# Mouse_STM32F401.net
KiCad netlist of a schematic drawn in EAGLE
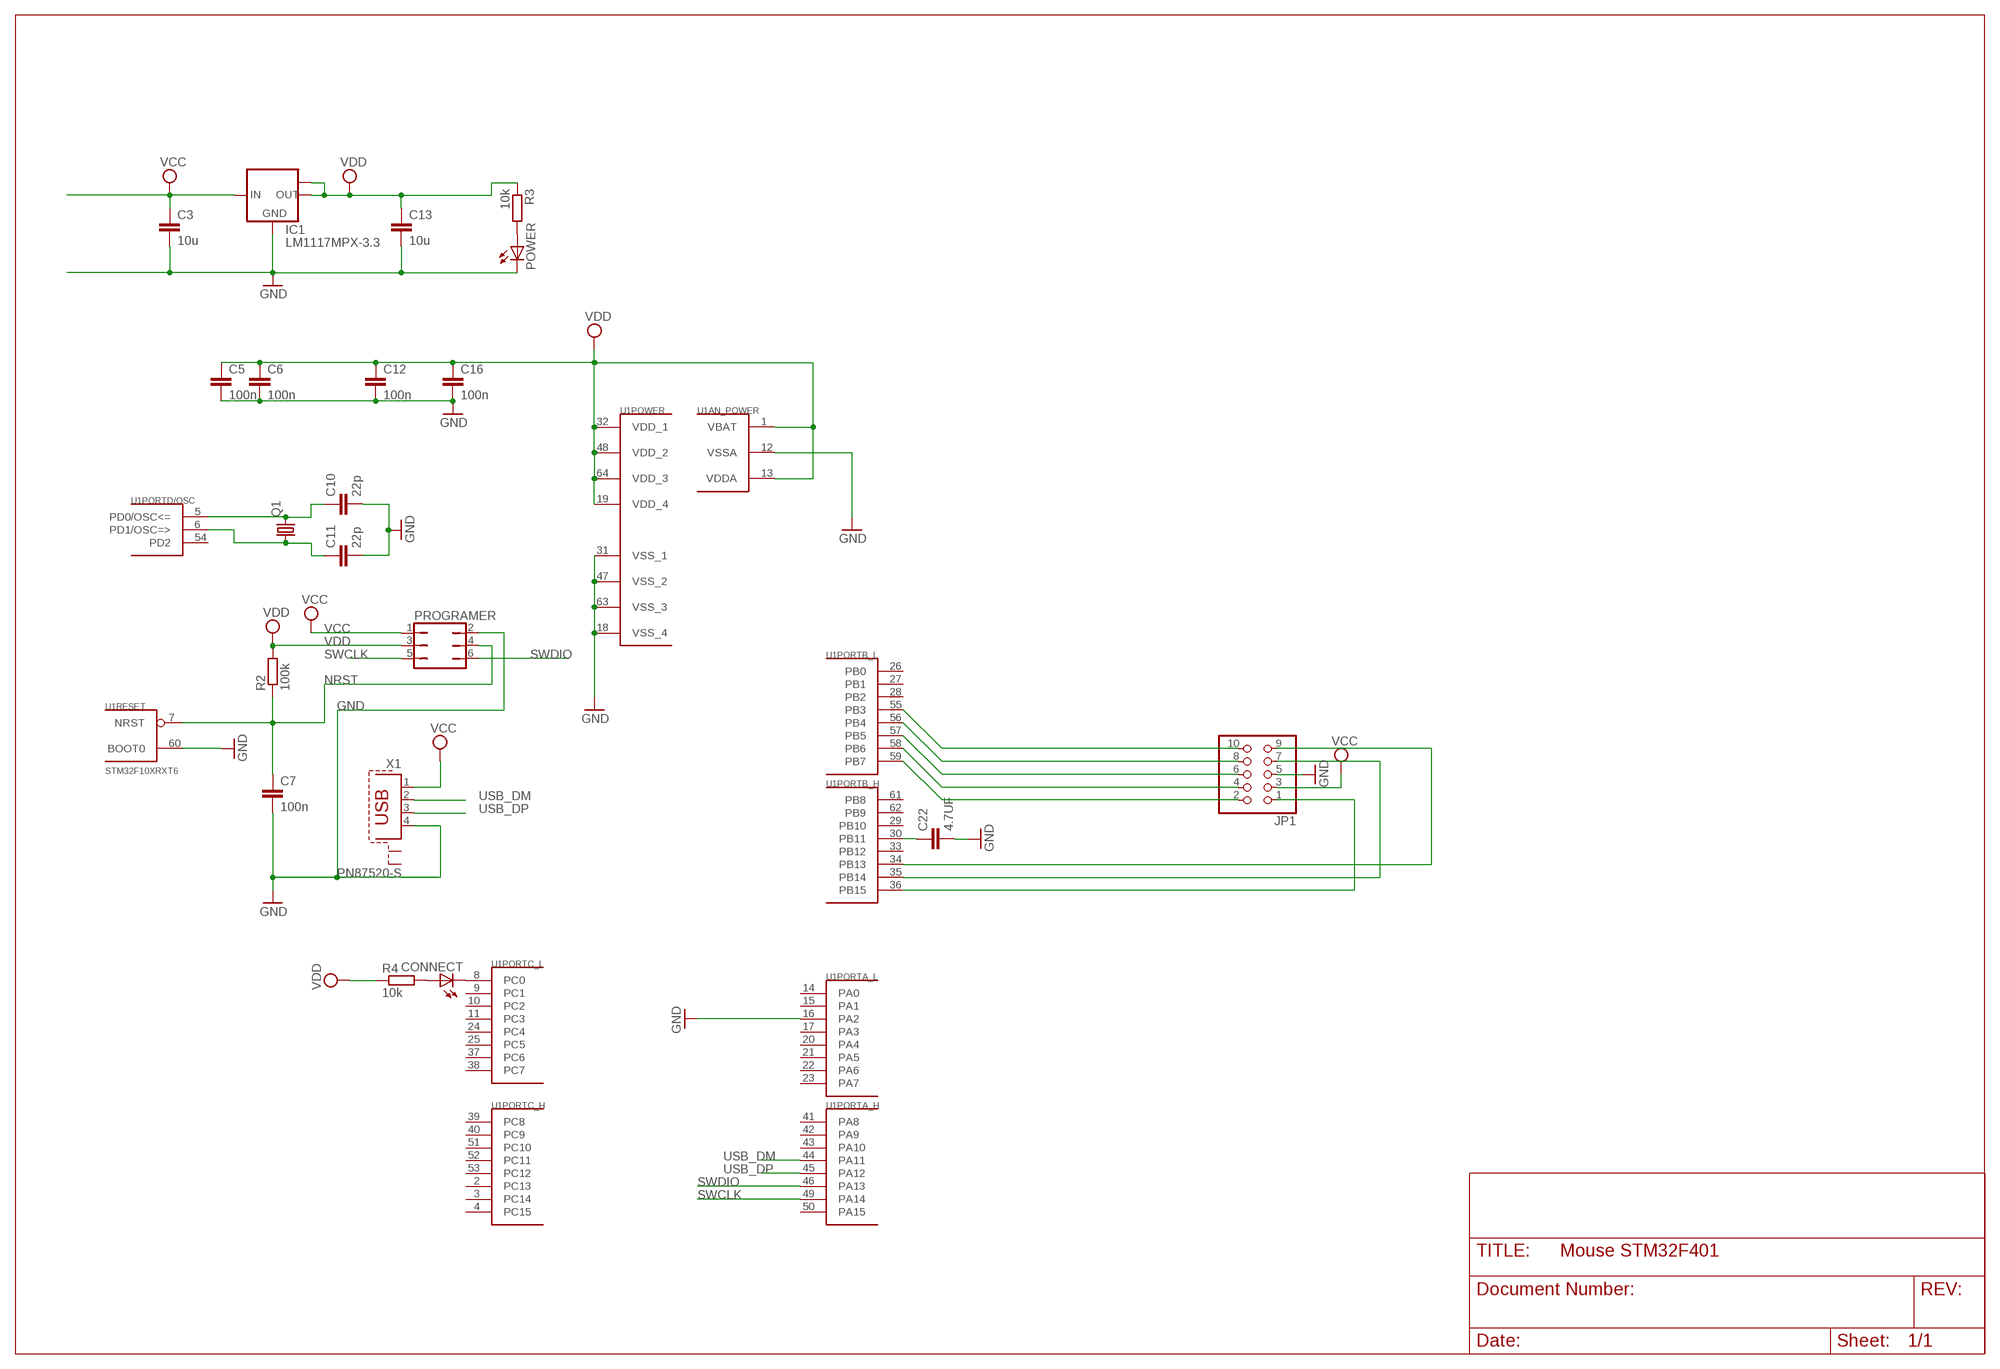
[diagram p0: schematic, sheet 1]

(export (version "E")
  (design (tool "Eeschema 10.0.6"))
  (components
    (comp (ref "C3")
      (value "10u")
      (footprint "eagle-import:C1206")
      (libsource (lib "eagle-import") (part "C-EUC1206"))
    )
    (comp (ref "C5")
      (value "100n")
      (footprint "eagle-import:C0603")
      (libsource (lib "eagle-import") (part "C-EUC0603"))
    )
    (comp (ref "C6")
      (value "100n")
      (footprint "eagle-import:C0603")
      (libsource (lib "eagle-import") (part "C-EUC0603"))
    )
    (comp (ref "C7")
      (value "100n")
      (footprint "eagle-import:C0603")
      (libsource (lib "eagle-import") (part "C-EUC0603"))
    )
    (comp (ref "C10")
      (value "22p")
      (footprint "eagle-import:C0603")
      (libsource (lib "eagle-import") (part "C-EUC0603"))
    )
    (comp (ref "C11")
      (value "22p")
      (footprint "eagle-import:C0603")
      (libsource (lib "eagle-import") (part "C-EUC0603"))
    )
    (comp (ref "C12")
      (value "100n")
      (footprint "eagle-import:C0603")
      (libsource (lib "eagle-import") (part "C-EUC0603"))
    )
    (comp (ref "C13")
      (value "10u")
      (footprint "eagle-import:C1206")
      (libsource (lib "eagle-import") (part "C-EUC1206"))
    )
    (comp (ref "C16")
      (value "100n")
      (footprint "eagle-import:C0603")
      (libsource (lib "eagle-import") (part "C-EUC0603"))
    )
    (comp (ref "C22")
      (value "4.7UF")
      (footprint "eagle-import:C1206")
      (libsource (lib "eagle-import") (part "C-EUC1206"))
    )
    (comp (ref "CONNECT")
      (value "LEDSML0805")
      (footprint "eagle-import:SML0805")
      (libsource (lib "eagle-import") (part "LEDSML0805"))
    )
    (comp (ref "IC1")
      (value "LM1117MPX-3.3")
      (footprint "eagle-import:SOT223")
      (libsource (lib "eagle-import") (part "LM1117MPX-3.3"))
    )
    (comp (ref "JP1")
      (value "PINHD-2X5")
      (footprint "eagle-import:2X05")
      (libsource (lib "eagle-import") (part "PINHD-2X5"))
    )
    (comp (ref "POWER")
      (value "LEDSML0805")
      (footprint "eagle-import:SML0805")
      (libsource (lib "eagle-import") (part "LEDSML0805"))
    )
    (comp (ref "PROGRAMER")
      (value "JP3Q")
      (footprint "eagle-import:JP3Q")
      (libsource (lib "eagle-import") (part "JP3Q"))
    )
    (comp (ref "Q1")
      (value "CRYSTALHC49S")
      (footprint "eagle-import:HC49_S")
      (libsource (lib "eagle-import") (part "CRYSTALHC49S"))
    )
    (comp (ref "R2")
      (value "100k")
      (footprint "eagle-import:R0603")
      (libsource (lib "eagle-import") (part "R-EU_R0603"))
    )
    (comp (ref "R3")
      (value "10k")
      (footprint "eagle-import:R0603")
      (libsource (lib "eagle-import") (part "R-EU_R0603"))
    )
    (comp (ref "R4")
      (value "10k")
      (footprint "eagle-import:R0603")
      (libsource (lib "eagle-import") (part "R-EU_R0603"))
    )
    (comp (ref "U1")
      (value "STM32F10XRXT6")
      (footprint "eagle-import:TQFP64")
      (libsource (lib "eagle-import") (part "STM32F10XRXT6"))
    )
    (comp (ref "X1")
      (value "PN87520-S")
      (footprint "eagle-import:PN87520-S")
      (libsource (lib "eagle-import") (part "PN87520-S"))
    )
  )
  (nets
    (net (code "1") (name "/NRST") (class "Default")
      (node (ref "C7") (pin "1") (pinfunction "1_1") (pintype "passive"))
      (node (ref "PROGRAMER") (pin "4") (pinfunction "4_4") (pintype "passive"))
      (node (ref "R2") (pin "1") (pinfunction "1_1") (pintype "passive"))
      (node (ref "U1") (pin "7") (pinfunction "NRST_7") (pintype "input"))
    )
    (net (code "2") (name "/SWCLK") (class "Default")
      (node (ref "PROGRAMER") (pin "5") (pinfunction "5_5") (pintype "passive"))
      (node (ref "U1") (pin "49") (pinfunction "PA14_49") (pintype "bidirectional"))
    )
    (net (code "3") (name "/SWDIO") (class "Default")
      (node (ref "PROGRAMER") (pin "6") (pinfunction "6_6") (pintype "passive"))
      (node (ref "U1") (pin "46") (pinfunction "PA13_46") (pintype "bidirectional"))
    )
    (net (code "4") (name "/USB_DM") (class "Default")
      (node (ref "U1") (pin "44") (pinfunction "PA11_44") (pintype "bidirectional"))
      (node (ref "X1") (pin "2") (pinfunction "2_2") (pintype "passive"))
    )
    (net (code "5") (name "/USB_DP") (class "Default")
      (node (ref "U1") (pin "45") (pinfunction "PA12_45") (pintype "bidirectional"))
      (node (ref "X1") (pin "3") (pinfunction "3_3") (pintype "passive"))
    )
    (net (code "6") (name "GND") (class "Default")
      (node (ref "C10") (pin "2") (pinfunction "2_2") (pintype "passive"))
      (node (ref "C11") (pin "2") (pinfunction "2_2") (pintype "passive"))
      (node (ref "C12") (pin "2") (pinfunction "2_2") (pintype "passive"))
      (node (ref "C13") (pin "2") (pinfunction "2_2") (pintype "passive"))
      (node (ref "C16") (pin "2") (pinfunction "2_2") (pintype "passive"))
      (node (ref "C22") (pin "2") (pinfunction "2_2") (pintype "passive"))
      (node (ref "C3") (pin "2") (pinfunction "2_2") (pintype "passive"))
      (node (ref "C5") (pin "2") (pinfunction "2_2") (pintype "passive"))
      (node (ref "C6") (pin "2") (pinfunction "2_2") (pintype "passive"))
      (node (ref "C7") (pin "2") (pinfunction "2_2") (pintype "passive"))
      (node (ref "IC1") (pin "1") (pinfunction "GND_1") (pintype "input"))
      (node (ref "JP1") (pin "5") (pinfunction "5_5") (pintype "passive"))
      (node (ref "POWER") (pin "C") (pinfunction "C_C") (pintype "passive"))
      (node (ref "PROGRAMER") (pin "2") (pinfunction "2_2") (pintype "passive"))
      (node (ref "U1") (pin "12") (pinfunction "VSSA_12") (pintype "power_in"))
      (node (ref "U1") (pin "16") (pinfunction "PA2_16") (pintype "bidirectional"))
      (node (ref "U1") (pin "18") (pinfunction "VSS_4_18") (pintype "power_in"))
      (node (ref "U1") (pin "31") (pinfunction "VSS_1_31") (pintype "power_in"))
      (node (ref "U1") (pin "47") (pinfunction "VSS_2_47") (pintype "power_in"))
      (node (ref "U1") (pin "60") (pinfunction "BOOT0_60") (pintype "input"))
      (node (ref "U1") (pin "63") (pinfunction "VSS_3_63") (pintype "power_in"))
      (node (ref "X1") (pin "4") (pinfunction "4_4") (pintype "passive"))
    )
    (net (code "7") (name "Net-(CONNECT-PadA)") (class "Default")
      (node (ref "CONNECT") (pin "A") (pinfunction "A_A") (pintype "passive"))
      (node (ref "R4") (pin "2") (pinfunction "2_2") (pintype "passive"))
    )
    (net (code "8") (name "Net-(POWER-PadA)") (class "Default")
      (node (ref "POWER") (pin "A") (pinfunction "A_A") (pintype "passive"))
      (node (ref "R3") (pin "2") (pinfunction "2_2") (pintype "passive"))
    )
    (net (code "9") (name "Net-(U1D-PB11)") (class "Default")
      (node (ref "C22") (pin "1") (pinfunction "1_1") (pintype "passive"))
      (node (ref "U1") (pin "30") (pinfunction "PB11_30") (pintype "bidirectional"))
    )
    (net (code "10") (name "Net-(U1D-PB13)") (class "Default")
      (node (ref "JP1") (pin "9") (pinfunction "9_9") (pintype "passive"))
      (node (ref "U1") (pin "34") (pinfunction "PB13_34") (pintype "bidirectional"))
    )
    (net (code "11") (name "Net-(U1D-PB14)") (class "Default")
      (node (ref "JP1") (pin "7") (pinfunction "7_7") (pintype "passive"))
      (node (ref "U1") (pin "35") (pinfunction "PB14_35") (pintype "bidirectional"))
    )
    (net (code "12") (name "Net-(U1D-PB15)") (class "Default")
      (node (ref "JP1") (pin "1") (pinfunction "1_1") (pintype "passive"))
      (node (ref "U1") (pin "36") (pinfunction "PB15_36") (pintype "bidirectional"))
    )
    (net (code "13") (name "Net-(U1E-PB3)") (class "Default")
      (node (ref "JP1") (pin "10") (pinfunction "10_10") (pintype "passive"))
      (node (ref "U1") (pin "55") (pinfunction "PB3_55") (pintype "bidirectional"))
    )
    (net (code "14") (name "Net-(U1E-PB4)") (class "Default")
      (node (ref "JP1") (pin "8") (pinfunction "8_8") (pintype "passive"))
      (node (ref "U1") (pin "56") (pinfunction "PB4_56") (pintype "bidirectional"))
    )
    (net (code "15") (name "Net-(U1E-PB5)") (class "Default")
      (node (ref "JP1") (pin "6") (pinfunction "6_6") (pintype "passive"))
      (node (ref "U1") (pin "57") (pinfunction "PB5_57") (pintype "bidirectional"))
    )
    (net (code "16") (name "Net-(U1E-PB6)") (class "Default")
      (node (ref "JP1") (pin "4") (pinfunction "4_4") (pintype "passive"))
      (node (ref "U1") (pin "58") (pinfunction "PB6_58") (pintype "bidirectional"))
    )
    (net (code "17") (name "Net-(U1E-PB7)") (class "Default")
      (node (ref "JP1") (pin "2") (pinfunction "2_2") (pintype "passive"))
      (node (ref "U1") (pin "59") (pinfunction "PB7_59") (pintype "bidirectional"))
    )
    (net (code "18") (name "Net-(U1G-PC0)") (class "Default")
      (node (ref "CONNECT") (pin "C") (pinfunction "C_C") (pintype "passive"))
      (node (ref "U1") (pin "8") (pinfunction "PC0_8") (pintype "bidirectional"))
    )
    (net (code "19") (name "Net-(U1H-PD0{slash}OSC<=)") (class "Default")
      (node (ref "C10") (pin "1") (pinfunction "1_1") (pintype "passive"))
      (node (ref "Q1") (pin "2") (pinfunction "2_2") (pintype "passive"))
      (node (ref "U1") (pin "5") (pinfunction "PD0/OSC<=_5") (pintype "bidirectional"))
    )
    (net (code "20") (name "Net-(U1H-PD1{slash}OSC=>)") (class "Default")
      (node (ref "C11") (pin "1") (pinfunction "1_1") (pintype "passive"))
      (node (ref "Q1") (pin "1") (pinfunction "1_1") (pintype "passive"))
      (node (ref "U1") (pin "6") (pinfunction "PD1/OSC=>_6") (pintype "bidirectional"))
    )
    (net (code "21") (name "VCC") (class "Default")
      (node (ref "C3") (pin "1") (pinfunction "1_1") (pintype "passive"))
      (node (ref "IC1") (pin "3") (pinfunction "IN_3") (pintype "input"))
      (node (ref "JP1") (pin "3") (pinfunction "3_3") (pintype "passive"))
      (node (ref "PROGRAMER") (pin "1") (pinfunction "1_1") (pintype "passive"))
      (node (ref "X1") (pin "1") (pinfunction "1_1") (pintype "passive"))
    )
    (net (code "22") (name "VDD") (class "Default")
      (node (ref "C12") (pin "1") (pinfunction "1_1") (pintype "passive"))
      (node (ref "C13") (pin "1") (pinfunction "1_1") (pintype "passive"))
      (node (ref "C16") (pin "1") (pinfunction "1_1") (pintype "passive"))
      (node (ref "C5") (pin "1") (pinfunction "1_1") (pintype "passive"))
      (node (ref "C6") (pin "1") (pinfunction "1_1") (pintype "passive"))
      (node (ref "IC1") (pin "2") (pinfunction "OUT_2") (pintype "passive"))
      (node (ref "IC1") (pin "TAB") (pinfunction "OUT1_TAB") (pintype "passive"))
      (node (ref "PROGRAMER") (pin "3") (pinfunction "3_3") (pintype "passive"))
      (node (ref "R2") (pin "2") (pinfunction "2_2") (pintype "passive"))
      (node (ref "R3") (pin "1") (pinfunction "1_1") (pintype "passive"))
      (node (ref "R4") (pin "1") (pinfunction "1_1") (pintype "passive"))
      (node (ref "U1") (pin "1") (pinfunction "VBAT_1") (pintype "power_in"))
      (node (ref "U1") (pin "13") (pinfunction "VDDA_13") (pintype "power_in"))
      (node (ref "U1") (pin "19") (pinfunction "VDD_4_19") (pintype "power_in"))
      (node (ref "U1") (pin "32") (pinfunction "VDD_1_32") (pintype "power_in"))
      (node (ref "U1") (pin "48") (pinfunction "VDD_2_48") (pintype "power_in"))
      (node (ref "U1") (pin "64") (pinfunction "VDD_3_64") (pintype "power_in"))
    )
    (net (code "23") (name "unconnected-(U1B-PA8-Pad41)") (class "Default")
      (node (ref "U1") (pin "41") (pinfunction "PA8_41") (pintype "bidirectional"))
    )
    (net (code "24") (name "unconnected-(U1B-PA9-Pad42)") (class "Default")
      (node (ref "U1") (pin "42") (pinfunction "PA9_42") (pintype "bidirectional"))
    )
    (net (code "25") (name "unconnected-(U1B-PA10-Pad43)") (class "Default")
      (node (ref "U1") (pin "43") (pinfunction "PA10_43") (pintype "bidirectional"))
    )
    (net (code "26") (name "unconnected-(U1B-PA15-Pad50)") (class "Default")
      (node (ref "U1") (pin "50") (pinfunction "PA15_50") (pintype "bidirectional"))
    )
    (net (code "27") (name "unconnected-(U1C-PA0-Pad14)") (class "Default")
      (node (ref "U1") (pin "14") (pinfunction "PA0_14") (pintype "bidirectional"))
    )
    (net (code "28") (name "unconnected-(U1C-PA1-Pad15)") (class "Default")
      (node (ref "U1") (pin "15") (pinfunction "PA1_15") (pintype "bidirectional"))
    )
    (net (code "29") (name "unconnected-(U1C-PA3-Pad17)") (class "Default")
      (node (ref "U1") (pin "17") (pinfunction "PA3_17") (pintype "bidirectional"))
    )
    (net (code "30") (name "unconnected-(U1C-PA4-Pad20)") (class "Default")
      (node (ref "U1") (pin "20") (pinfunction "PA4_20") (pintype "bidirectional"))
    )
    (net (code "31") (name "unconnected-(U1C-PA5-Pad21)") (class "Default")
      (node (ref "U1") (pin "21") (pinfunction "PA5_21") (pintype "bidirectional"))
    )
    (net (code "32") (name "unconnected-(U1C-PA6-Pad22)") (class "Default")
      (node (ref "U1") (pin "22") (pinfunction "PA6_22") (pintype "bidirectional"))
    )
    (net (code "33") (name "unconnected-(U1C-PA7-Pad23)") (class "Default")
      (node (ref "U1") (pin "23") (pinfunction "PA7_23") (pintype "bidirectional"))
    )
    (net (code "34") (name "unconnected-(U1D-PB8-Pad61)") (class "Default")
      (node (ref "U1") (pin "61") (pinfunction "PB8_61") (pintype "bidirectional"))
    )
    (net (code "35") (name "unconnected-(U1D-PB9-Pad62)") (class "Default")
      (node (ref "U1") (pin "62") (pinfunction "PB9_62") (pintype "bidirectional"))
    )
    (net (code "36") (name "unconnected-(U1D-PB10-Pad29)") (class "Default")
      (node (ref "U1") (pin "29") (pinfunction "PB10_29") (pintype "bidirectional"))
    )
    (net (code "37") (name "unconnected-(U1D-PB12-Pad33)") (class "Default")
      (node (ref "U1") (pin "33") (pinfunction "PB12_33") (pintype "bidirectional"))
    )
    (net (code "38") (name "unconnected-(U1E-PB0-Pad26)") (class "Default")
      (node (ref "U1") (pin "26") (pinfunction "PB0_26") (pintype "bidirectional"))
    )
    (net (code "39") (name "unconnected-(U1E-PB1-Pad27)") (class "Default")
      (node (ref "U1") (pin "27") (pinfunction "PB1_27") (pintype "bidirectional"))
    )
    (net (code "40") (name "unconnected-(U1E-PB2-Pad28)") (class "Default")
      (node (ref "U1") (pin "28") (pinfunction "PB2_28") (pintype "bidirectional"))
    )
    (net (code "41") (name "unconnected-(U1F-PC8-Pad39)") (class "Default")
      (node (ref "U1") (pin "39") (pinfunction "PC8_39") (pintype "bidirectional"))
    )
    (net (code "42") (name "unconnected-(U1F-PC9-Pad40)") (class "Default")
      (node (ref "U1") (pin "40") (pinfunction "PC9_40") (pintype "bidirectional"))
    )
    (net (code "43") (name "unconnected-(U1F-PC10-Pad51)") (class "Default")
      (node (ref "U1") (pin "51") (pinfunction "PC10_51") (pintype "bidirectional"))
    )
    (net (code "44") (name "unconnected-(U1F-PC11-Pad52)") (class "Default")
      (node (ref "U1") (pin "52") (pinfunction "PC11_52") (pintype "bidirectional"))
    )
    (net (code "45") (name "unconnected-(U1F-PC12-Pad53)") (class "Default")
      (node (ref "U1") (pin "53") (pinfunction "PC12_53") (pintype "bidirectional"))
    )
    (net (code "46") (name "unconnected-(U1F-PC13-Pad2)") (class "Default")
      (node (ref "U1") (pin "2") (pinfunction "PC13_2") (pintype "bidirectional"))
    )
    (net (code "47") (name "unconnected-(U1F-PC14-Pad3)") (class "Default")
      (node (ref "U1") (pin "3") (pinfunction "PC14_3") (pintype "bidirectional"))
    )
    (net (code "48") (name "unconnected-(U1F-PC15-Pad4)") (class "Default")
      (node (ref "U1") (pin "4") (pinfunction "PC15_4") (pintype "bidirectional"))
    )
    (net (code "49") (name "unconnected-(U1G-PC1-Pad9)") (class "Default")
      (node (ref "U1") (pin "9") (pinfunction "PC1_9") (pintype "bidirectional"))
    )
    (net (code "50") (name "unconnected-(U1G-PC2-Pad10)") (class "Default")
      (node (ref "U1") (pin "10") (pinfunction "PC2_10") (pintype "bidirectional"))
    )
    (net (code "51") (name "unconnected-(U1G-PC3-Pad11)") (class "Default")
      (node (ref "U1") (pin "11") (pinfunction "PC3_11") (pintype "bidirectional"))
    )
    (net (code "52") (name "unconnected-(U1G-PC4-Pad24)") (class "Default")
      (node (ref "U1") (pin "24") (pinfunction "PC4_24") (pintype "bidirectional"))
    )
    (net (code "53") (name "unconnected-(U1G-PC5-Pad25)") (class "Default")
      (node (ref "U1") (pin "25") (pinfunction "PC5_25") (pintype "bidirectional"))
    )
    (net (code "54") (name "unconnected-(U1G-PC6-Pad37)") (class "Default")
      (node (ref "U1") (pin "37") (pinfunction "PC6_37") (pintype "bidirectional"))
    )
    (net (code "55") (name "unconnected-(U1G-PC7-Pad38)") (class "Default")
      (node (ref "U1") (pin "38") (pinfunction "PC7_38") (pintype "bidirectional"))
    )
    (net (code "56") (name "unconnected-(U1H-PD2-Pad54)") (class "Default")
      (node (ref "U1") (pin "54") (pinfunction "PD2_54") (pintype "bidirectional"))
    )
    (net (code "57") (name "unconnected-(X1-PadS1)") (class "Default")
      (node (ref "X1") (pin "S1") (pinfunction "S1_S1") (pintype "passive"))
    )
    (net (code "58") (name "unconnected-(X1-PadS2)") (class "Default")
      (node (ref "X1") (pin "S2") (pinfunction "S2_S2") (pintype "passive"))
    )
  )
)
